# mcp_basic.net
KiCad netlist of a schematic drawn in EAGLE
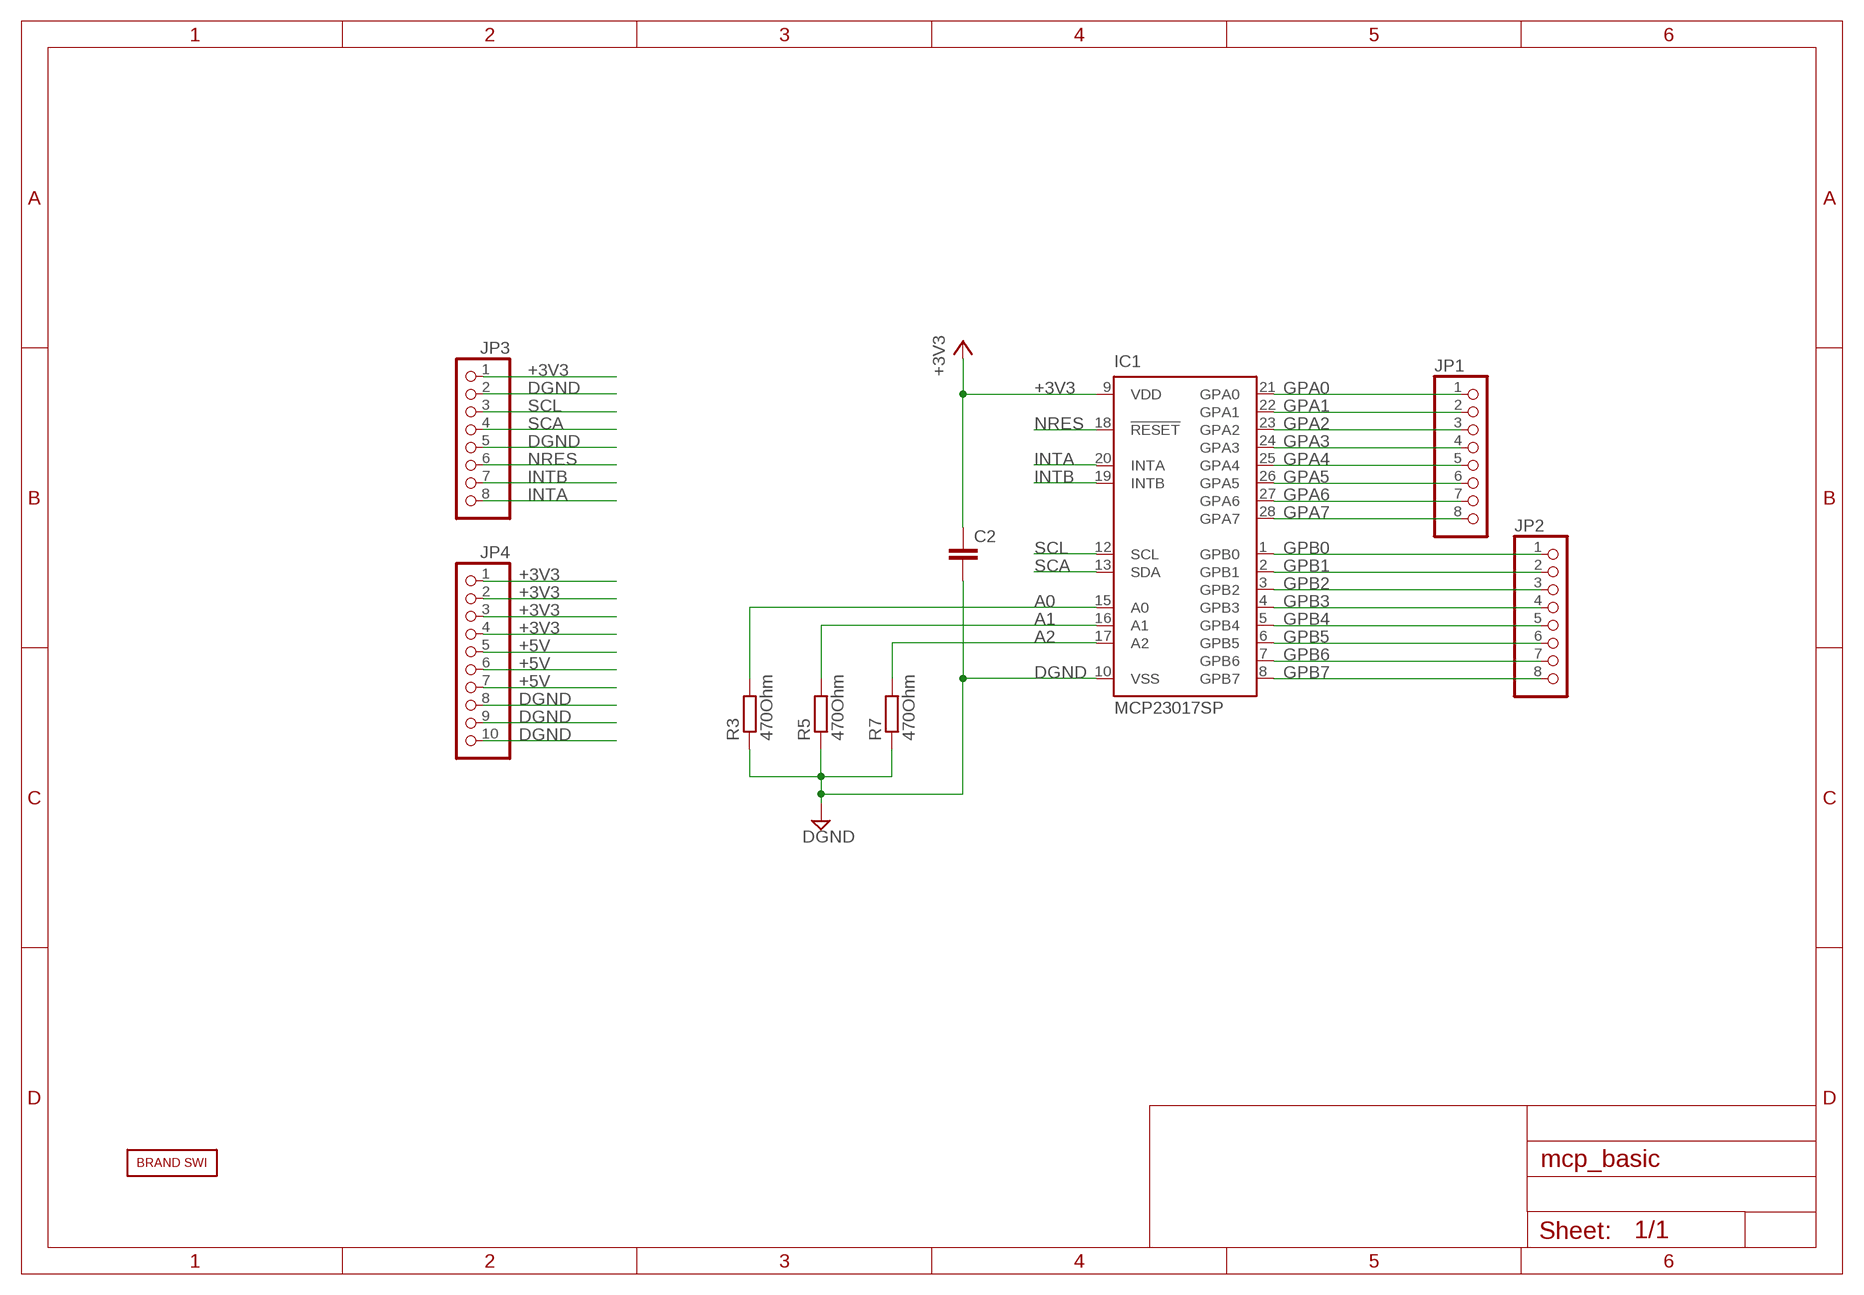
[diagram p0: schematic, sheet 1]

(export (version "E")
  (design (tool "Eeschema 10.0.6"))
  (components
    (comp (ref "C2")
      (value "C-EUC1210")
      (footprint "eagle-import:C1210")
      (libsource (lib "eagle-import") (part "C-EUC1210"))
    )
    (comp (ref "IC1")
      (value "MCP23017SP")
      (footprint "eagle-import:DIL28-3")
      (fields (field (name "MF") "MICROCHIP") (field (name "MPN") "MCP23017-E/SP"))
      (libsource (lib "eagle-import") (part "MCP23017SP"))
    )
    (comp (ref "JP1")
      (value "PINHD-1X8")
      (footprint "eagle-import:1X08")
      (libsource (lib "eagle-import") (part "PINHD-1X8"))
    )
    (comp (ref "JP2")
      (value "PINHD-1X8")
      (footprint "eagle-import:1X08")
      (libsource (lib "eagle-import") (part "PINHD-1X8"))
    )
    (comp (ref "JP3")
      (value "PINHD-1X8")
      (footprint "eagle-import:1X08")
      (libsource (lib "eagle-import") (part "PINHD-1X8"))
    )
    (comp (ref "JP4")
      (value "PINHD-1X10")
      (footprint "eagle-import:1X10")
      (libsource (lib "eagle-import") (part "PINHD-1X10"))
    )
    (comp (ref "R3")
      (value "470Ohm")
      (footprint "eagle-import:R0805")
      (libsource (lib "eagle-import") (part "R-EU_R0805"))
    )
    (comp (ref "R5")
      (value "470Ohm")
      (footprint "eagle-import:R0805")
      (libsource (lib "eagle-import") (part "R-EU_R0805"))
    )
    (comp (ref "R7")
      (value "470Ohm")
      (footprint "eagle-import:R0805")
      (libsource (lib "eagle-import") (part "R-EU_R0805"))
    )
    (comp (ref "U$2")
      (value "BRAND_SWI5X7")
      (footprint "eagle-import:BRAND_SWI_5X7")
      (libsource (lib "eagle-import") (part "BRAND_SWI5X7"))
    )
  )
  (nets
    (net (code "1") (name "+3V3") (class "Default")
      (node (ref "C2") (pin "1") (pinfunction "1_1") (pintype "passive"))
      (node (ref "IC1") (pin "9") (pinfunction "VDD_9") (pintype "power_in"))
      (node (ref "JP3") (pin "1") (pinfunction "1_1") (pintype "passive"))
      (node (ref "JP4") (pin "1") (pinfunction "1_1") (pintype "passive"))
      (node (ref "JP4") (pin "2") (pinfunction "2_2") (pintype "passive"))
      (node (ref "JP4") (pin "3") (pinfunction "3_3") (pintype "passive"))
      (node (ref "JP4") (pin "4") (pinfunction "4_4") (pintype "passive"))
    )
    (net (code "2") (name "/+5V") (class "Default")
      (node (ref "JP4") (pin "5") (pinfunction "5_5") (pintype "passive"))
      (node (ref "JP4") (pin "6") (pinfunction "6_6") (pintype "passive"))
      (node (ref "JP4") (pin "7") (pinfunction "7_7") (pintype "passive"))
    )
    (net (code "3") (name "/A0") (class "Default")
      (node (ref "IC1") (pin "15") (pinfunction "A0_15") (pintype "input"))
      (node (ref "R3") (pin "2") (pinfunction "2_2") (pintype "passive"))
    )
    (net (code "4") (name "/A1") (class "Default")
      (node (ref "IC1") (pin "16") (pinfunction "A1_16") (pintype "input"))
      (node (ref "R5") (pin "2") (pinfunction "2_2") (pintype "passive"))
    )
    (net (code "5") (name "/A2") (class "Default")
      (node (ref "IC1") (pin "17") (pinfunction "A2_17") (pintype "input"))
      (node (ref "R7") (pin "2") (pinfunction "2_2") (pintype "passive"))
    )
    (net (code "6") (name "/GPA0") (class "Default")
      (node (ref "IC1") (pin "21") (pinfunction "GPA0_21") (pintype "bidirectional"))
      (node (ref "JP1") (pin "1") (pinfunction "1_1") (pintype "passive"))
    )
    (net (code "7") (name "/GPA1") (class "Default")
      (node (ref "IC1") (pin "22") (pinfunction "GPA1_22") (pintype "bidirectional"))
      (node (ref "JP1") (pin "2") (pinfunction "2_2") (pintype "passive"))
    )
    (net (code "8") (name "/GPA2") (class "Default")
      (node (ref "IC1") (pin "23") (pinfunction "GPA2_23") (pintype "bidirectional"))
      (node (ref "JP1") (pin "3") (pinfunction "3_3") (pintype "passive"))
    )
    (net (code "9") (name "/GPA3") (class "Default")
      (node (ref "IC1") (pin "24") (pinfunction "GPA3_24") (pintype "bidirectional"))
      (node (ref "JP1") (pin "4") (pinfunction "4_4") (pintype "passive"))
    )
    (net (code "10") (name "/GPA4") (class "Default")
      (node (ref "IC1") (pin "25") (pinfunction "GPA4_25") (pintype "bidirectional"))
      (node (ref "JP1") (pin "5") (pinfunction "5_5") (pintype "passive"))
    )
    (net (code "11") (name "/GPA5") (class "Default")
      (node (ref "IC1") (pin "26") (pinfunction "GPA5_26") (pintype "bidirectional"))
      (node (ref "JP1") (pin "6") (pinfunction "6_6") (pintype "passive"))
    )
    (net (code "12") (name "/GPA6") (class "Default")
      (node (ref "IC1") (pin "27") (pinfunction "GPA6_27") (pintype "bidirectional"))
      (node (ref "JP1") (pin "7") (pinfunction "7_7") (pintype "passive"))
    )
    (net (code "13") (name "/GPA7") (class "Default")
      (node (ref "IC1") (pin "28") (pinfunction "GPA7_28") (pintype "bidirectional"))
      (node (ref "JP1") (pin "8") (pinfunction "8_8") (pintype "passive"))
    )
    (net (code "14") (name "/GPB0") (class "Default")
      (node (ref "IC1") (pin "1") (pinfunction "GPB0_1") (pintype "bidirectional"))
      (node (ref "JP2") (pin "1") (pinfunction "1_1") (pintype "passive"))
    )
    (net (code "15") (name "/GPB1") (class "Default")
      (node (ref "IC1") (pin "2") (pinfunction "GPB1_2") (pintype "bidirectional"))
      (node (ref "JP2") (pin "2") (pinfunction "2_2") (pintype "passive"))
    )
    (net (code "16") (name "/GPB2") (class "Default")
      (node (ref "IC1") (pin "3") (pinfunction "GPB2_3") (pintype "bidirectional"))
      (node (ref "JP2") (pin "3") (pinfunction "3_3") (pintype "passive"))
    )
    (net (code "17") (name "/GPB3") (class "Default")
      (node (ref "IC1") (pin "4") (pinfunction "GPB3_4") (pintype "bidirectional"))
      (node (ref "JP2") (pin "4") (pinfunction "4_4") (pintype "passive"))
    )
    (net (code "18") (name "/GPB4") (class "Default")
      (node (ref "IC1") (pin "5") (pinfunction "GPB4_5") (pintype "bidirectional"))
      (node (ref "JP2") (pin "5") (pinfunction "5_5") (pintype "passive"))
    )
    (net (code "19") (name "/GPB5") (class "Default")
      (node (ref "IC1") (pin "6") (pinfunction "GPB5_6") (pintype "bidirectional"))
      (node (ref "JP2") (pin "6") (pinfunction "6_6") (pintype "passive"))
    )
    (net (code "20") (name "/GPB6") (class "Default")
      (node (ref "IC1") (pin "7") (pinfunction "GPB6_7") (pintype "bidirectional"))
      (node (ref "JP2") (pin "7") (pinfunction "7_7") (pintype "passive"))
    )
    (net (code "21") (name "/GPB7") (class "Default")
      (node (ref "IC1") (pin "8") (pinfunction "GPB7_8") (pintype "bidirectional"))
      (node (ref "JP2") (pin "8") (pinfunction "8_8") (pintype "passive"))
    )
    (net (code "22") (name "/INTA") (class "Default")
      (node (ref "IC1") (pin "20") (pinfunction "INTA_20") (pintype "output"))
      (node (ref "JP3") (pin "8") (pinfunction "8_8") (pintype "passive"))
    )
    (net (code "23") (name "/INTB") (class "Default")
      (node (ref "IC1") (pin "19") (pinfunction "INTB_19") (pintype "output"))
      (node (ref "JP3") (pin "7") (pinfunction "7_7") (pintype "passive"))
    )
    (net (code "24") (name "/NRES") (class "Default")
      (node (ref "IC1") (pin "18") (pinfunction "~{RESET}_18") (pintype "input"))
      (node (ref "JP3") (pin "6") (pinfunction "6_6") (pintype "passive"))
    )
    (net (code "25") (name "/SCA") (class "Default")
      (node (ref "IC1") (pin "13") (pinfunction "SDA_13") (pintype "bidirectional"))
      (node (ref "JP3") (pin "4") (pinfunction "4_4") (pintype "passive"))
    )
    (net (code "26") (name "/SCL") (class "Default")
      (node (ref "IC1") (pin "12") (pinfunction "SCL_12") (pintype "input"))
      (node (ref "JP3") (pin "3") (pinfunction "3_3") (pintype "passive"))
    )
    (net (code "27") (name "DGND") (class "Default")
      (node (ref "C2") (pin "2") (pinfunction "2_2") (pintype "passive"))
      (node (ref "IC1") (pin "10") (pinfunction "VSS_10") (pintype "power_in"))
      (node (ref "JP3") (pin "2") (pinfunction "2_2") (pintype "passive"))
      (node (ref "JP3") (pin "5") (pinfunction "5_5") (pintype "passive"))
      (node (ref "JP4") (pin "10") (pinfunction "10_10") (pintype "passive"))
      (node (ref "JP4") (pin "8") (pinfunction "8_8") (pintype "passive"))
      (node (ref "JP4") (pin "9") (pinfunction "9_9") (pintype "passive"))
      (node (ref "R3") (pin "1") (pinfunction "1_1") (pintype "passive"))
      (node (ref "R5") (pin "1") (pinfunction "1_1") (pintype "passive"))
      (node (ref "R7") (pin "1") (pinfunction "1_1") (pintype "passive"))
    )
  )
)
